# analog.net
KiCad netlist of a schematic drawn in Altium Designer
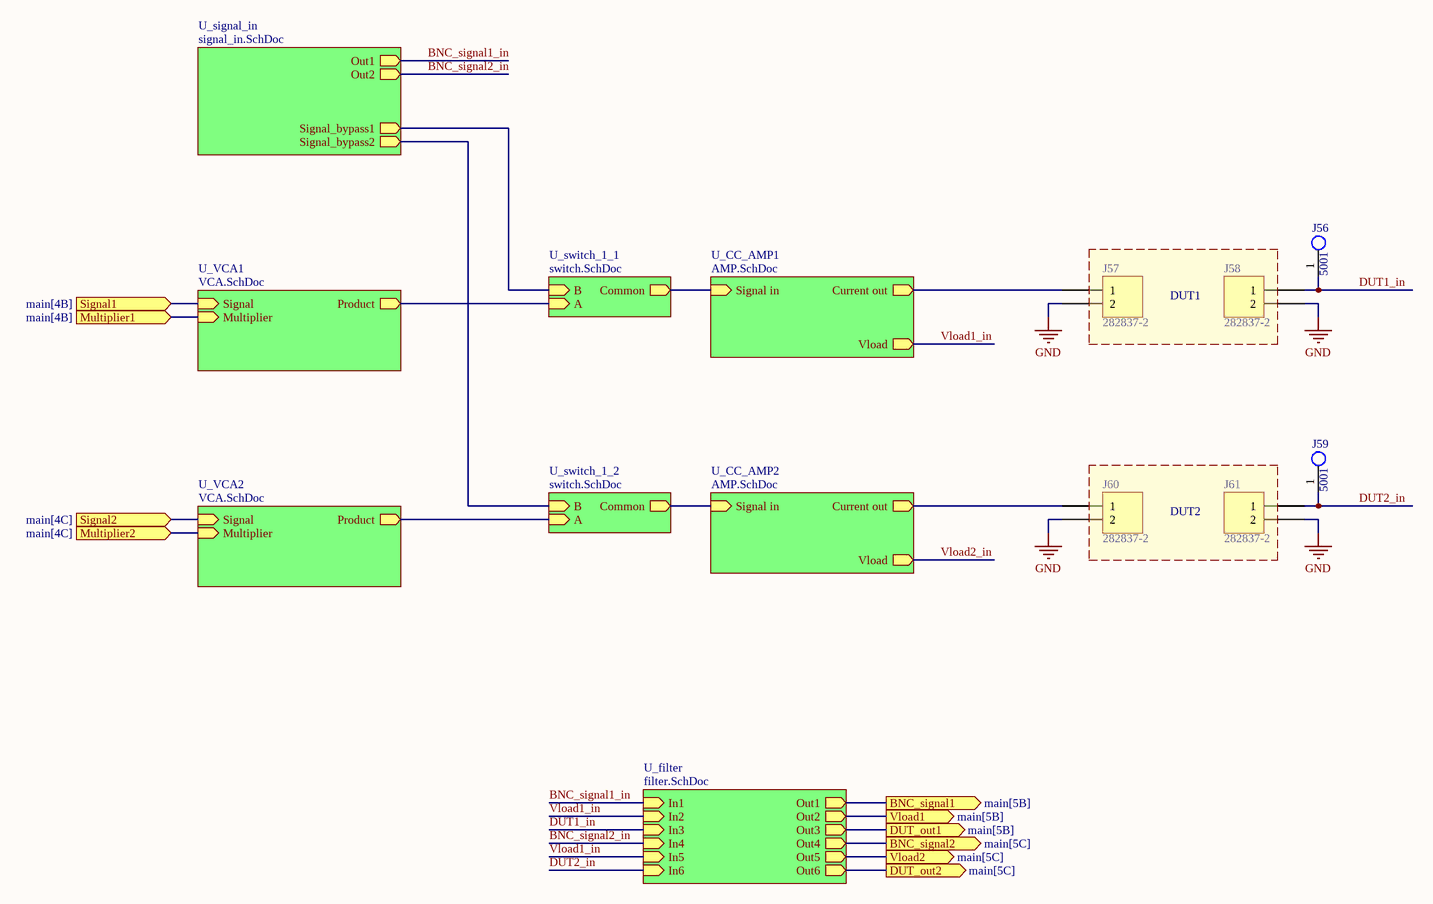
[diagram p0: analog.SchDoc]

(export (version "E")
  (design (tool "Eeschema 10.0.6"))
  (components
    (comp (ref "J56")
      (value "5001")
      (footprint "FP-5001-MFG")
      (description "PC TEST POINT MINIATURE BLACK")
      (libsource (lib "za_koncar") (part "CMP-2000-05181-2"))
    )
    (comp (ref "J57")
      (value "282837-2")
      (footprint "TE 282837-2")
      (description "TERM BLK 2P SIDE ENT 5.08MM PCB")
      (fields (field (name "MANUFACTURER") "TE Connectivity AMP Connectors") (field (name "VOLTAGE") "300 V"))
      (libsource (lib "") (part "2 Pin_1"))
    )
    (comp (ref "J58")
      (value "282837-2")
      (footprint "TE 282837-2")
      (description "TERM BLK 2P SIDE ENT 5.08MM PCB")
      (fields (field (name "MANUFACTURER") "TE Connectivity AMP Connectors") (field (name "VOLTAGE") "300 V"))
      (libsource (lib "Celestial Altium Library - altium_library") (part "2 Pin"))
    )
    (comp (ref "J59")
      (value "5001")
      (footprint "FP-5001-MFG")
      (description "PC TEST POINT MINIATURE BLACK")
      (libsource (lib "za_koncar") (part "CMP-2000-05181-2"))
    )
    (comp (ref "J60")
      (value "282837-2")
      (footprint "TE 282837-2")
      (description "TERM BLK 2P SIDE ENT 5.08MM PCB")
      (fields (field (name "MANUFACTURER") "TE Connectivity AMP Connectors") (field (name "VOLTAGE") "300 V"))
      (libsource (lib "") (part "2 Pin_1"))
    )
    (comp (ref "J61")
      (value "282837-2")
      (footprint "TE 282837-2")
      (description "TERM BLK 2P SIDE ENT 5.08MM PCB")
      (fields (field (name "MANUFACTURER") "TE Connectivity AMP Connectors") (field (name "VOLTAGE") "300 V"))
      (libsource (lib "Celestial Altium Library - altium_library") (part "2 Pin"))
    )
  )
  (nets
    (net (code "7") (name "/Current out") (class "Default")
      (node (ref "J60") (pin "1") (pinfunction "1_1") (pintype "passive"))
    )
    (net (code "8") (name "/Current out_1") (class "Default")
      (node (ref "J57") (pin "1") (pinfunction "1_1") (pintype "passive"))
    )
    (net (code "9") (name "/DUT1_in") (class "Default")
      (node (ref "J56") (pin "1") (pinfunction "1_1") (pintype "passive"))
      (node (ref "J58") (pin "1") (pinfunction "1_1") (pintype "passive"))
    )
    (net (code "10") (name "/DUT2_in") (class "Default")
      (node (ref "J59") (pin "1") (pinfunction "1_1") (pintype "passive"))
      (node (ref "J61") (pin "1") (pinfunction "1_1") (pintype "passive"))
    )
    (net (code "25") (name "GND") (class "Default")
      (node (ref "J57") (pin "2") (pinfunction "2_2") (pintype "passive"))
      (node (ref "J58") (pin "2") (pinfunction "2_2") (pintype "passive"))
      (node (ref "J60") (pin "2") (pinfunction "2_2") (pintype "passive"))
      (node (ref "J61") (pin "2") (pinfunction "2_2") (pintype "passive"))
    )
  )
)
